# Mecanique.net
KiCad netlist of a schematic drawn in Altium Designer
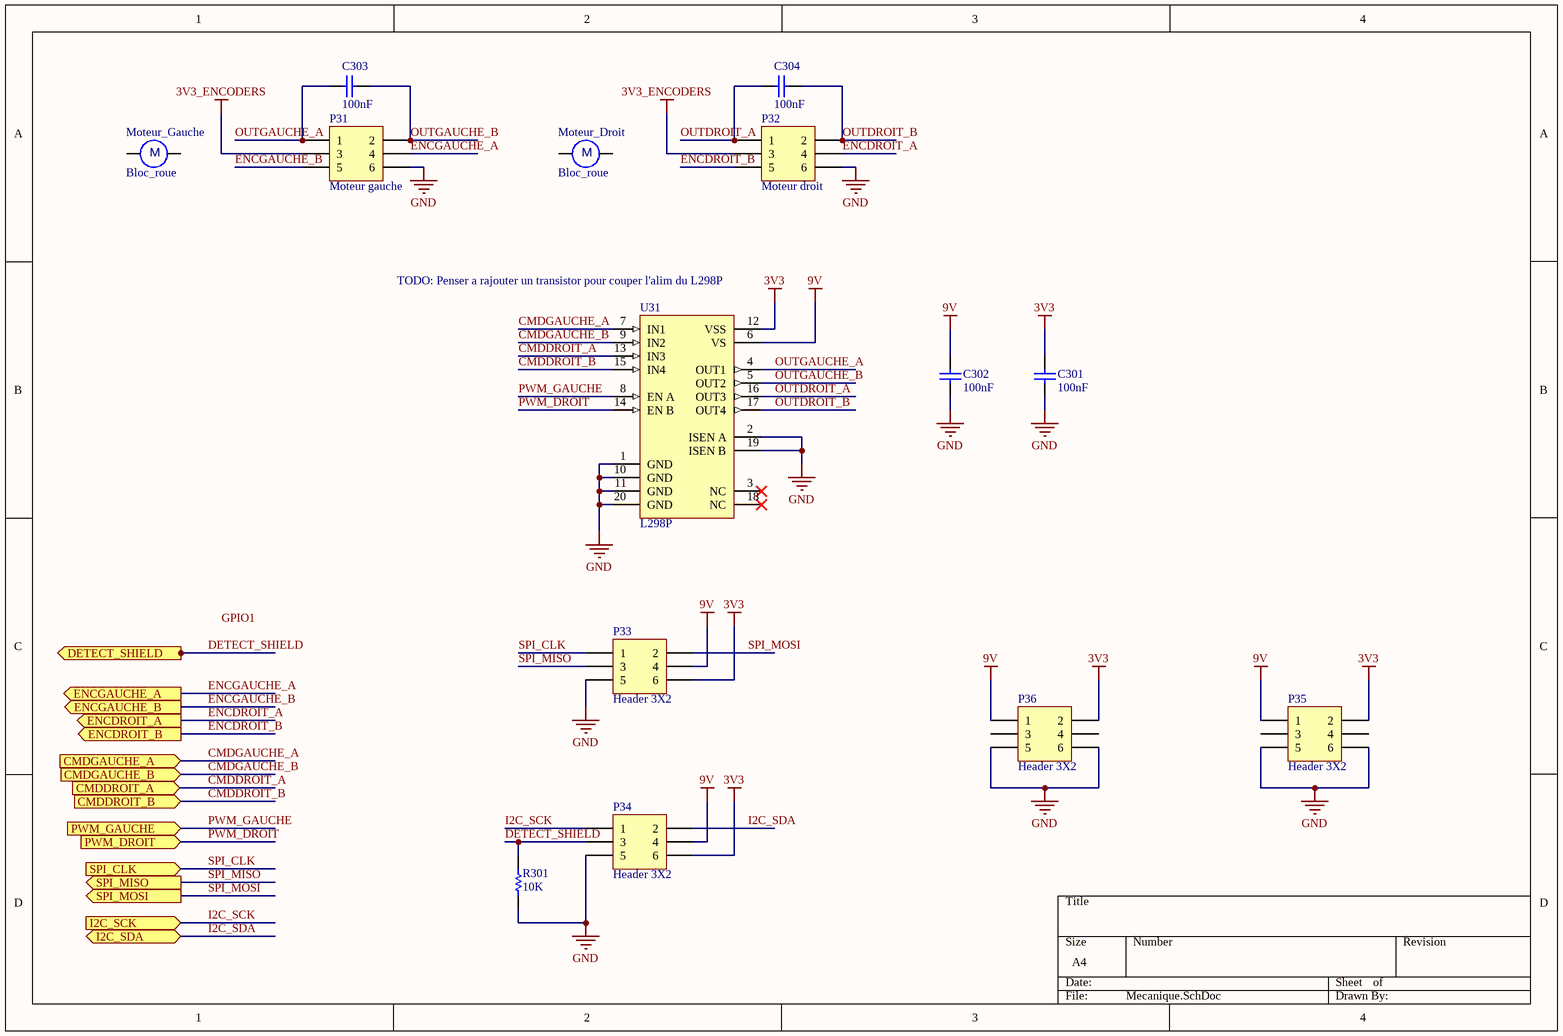
[diagram p0: Mecanique.SchDoc]

(export (version "E")
  (design (tool "Eeschema 10.0.6"))
  (components
    (comp (ref "C301")
      (value "100nF")
      (footprint "CAPC1206(3216)170_L")
      (description "CAP 100nF 50V ±10% 1206 (3216 Metric) Thickness 1.7mm SMD")
      (fields (field (name "TOLERANCE") "Â±10%") (field (name "Comment") "CAP 100nF"))
      (libsource (lib "Altium Content Vault") (part "CMP-1037-04201-1"))
    )
    (comp (ref "C302")
      (value "100nF")
      (footprint "CAPC1206(3216)170_L")
      (description "CAP 100nF 50V ±10% 1206 (3216 Metric) Thickness 1.7mm SMD")
      (fields (field (name "TOLERANCE") "Â±10%") (field (name "Comment") "CAP 100nF"))
      (libsource (lib "Altium Content Vault") (part "CMP-1037-04201-1"))
    )
    (comp (ref "C303")
      (value "100nF")
      (footprint "CAPC1206(3216)170_L")
      (description "CAP 100nF 50V ±10% 1206 (3216 Metric) Thickness 1.7mm SMD")
      (fields (field (name "TOLERANCE") "Â±10%") (field (name "Comment") "CAP 100nF"))
      (libsource (lib "Altium Content Vault") (part "CMP-1037-04201-1"))
    )
    (comp (ref "C304")
      (value "100nF")
      (footprint "CAPC1206(3216)170_L")
      (description "CAP 100nF 50V ±10% 1206 (3216 Metric) Thickness 1.7mm SMD")
      (fields (field (name "TOLERANCE") "Â±10%") (field (name "Comment") "CAP 100nF"))
      (libsource (lib "Altium Content Vault") (part "CMP-1037-04201-1"))
    )
    (comp (ref "Moteur_Droit")
      (value "Bloc_roue")
      (footprint "Bloc roue")
      (libsource (lib "Dumber 2015") (part "Bloc_roue"))
    )
    (comp (ref "Moteur_Gauche")
      (value "Bloc_roue")
      (footprint "Bloc roue")
      (libsource (lib "Dumber 2015") (part "Bloc_roue"))
    )
    (comp (ref "P31")
      (value "Moteur gauche")
      (footprint "HDR2X3")
      (description "Header, 3-Pin, Dual row")
      (fields (field (name "PUBLISHER") "Altium Limited"))
      (libsource (lib "Miscellaneous Connectors") (part "Header 3X2"))
    )
    (comp (ref "P32")
      (value "Moteur droit")
      (footprint "HDR2X3")
      (description "Header, 3-Pin, Dual row")
      (fields (field (name "PUBLISHER") "Altium Limited"))
      (libsource (lib "Miscellaneous Connectors") (part "Header 3X2"))
    )
    (comp (ref "P33")
      (value "Header 3X2")
      (footprint "HDR2X3")
      (description "Header, 3-Pin, Dual row")
      (fields (field (name "PUBLISHER") "Altium Limited"))
      (libsource (lib "Miscellaneous Connectors") (part "Header 3X2"))
    )
    (comp (ref "P34")
      (value "Header 3X2")
      (footprint "HDR2X3")
      (description "Header, 3-Pin, Dual row")
      (fields (field (name "PUBLISHER") "Altium Limited"))
      (libsource (lib "Miscellaneous Connectors") (part "Header 3X2"))
    )
    (comp (ref "P35")
      (value "Header 3X2")
      (footprint "HDR2X3")
      (description "Header, 3-Pin, Dual row")
      (fields (field (name "PUBLISHER") "Altium Limited"))
      (libsource (lib "Miscellaneous Connectors") (part "Header 3X2"))
    )
    (comp (ref "P36")
      (value "Header 3X2")
      (footprint "HDR2X3")
      (description "Header, 3-Pin, Dual row")
      (fields (field (name "PUBLISHER") "Altium Limited"))
      (libsource (lib "Miscellaneous Connectors") (part "Header 3X2"))
    )
    (comp (ref "R301")
      (value "10K")
      (footprint "RESC1206(3216)_M")
      (description "10K 0.25W 5% 1206 (3216 Metric)  SMD")
      (fields (field (name "POWER") "0.25 W") (field (name "TOLERANCE") "5 %"))
      (libsource (lib "Altium Content Vault") (part "CMP-1014-00098-1"))
    )
    (comp (ref "U31")
      (value "L298P")
      (footprint "PowerSO20_N")
      (description "Dual Full Bridge Driver")
      (fields (field (name "PUBLISHER") "Altium Limited"))
      (libsource (lib "ST Interface DC Motor Controller") (part "L298P"))
    )
  )
  (nets
    (net (code "1") (name "/CMDDROIT_A") (class "Default")
      (node (ref "U31") (pin "13") (pinfunction "IN3_13") (pintype "input"))
    )
    (net (code "2") (name "/CMDDROIT_B") (class "Default")
      (node (ref "U31") (pin "15") (pinfunction "IN4_15") (pintype "input"))
    )
    (net (code "3") (name "/CMDGAUCHE_A") (class "Default")
      (node (ref "U31") (pin "7") (pinfunction "IN1_7") (pintype "input"))
    )
    (net (code "4") (name "/CMDGAUCHE_B") (class "Default")
      (node (ref "U31") (pin "9") (pinfunction "IN2_9") (pintype "input"))
    )
    (net (code "5") (name "/DETECT_SHIELD") (class "Default")
      (node (ref "P34") (pin "3") (pinfunction "3_3") (pintype "passive"))
      (node (ref "R301") (pin "1") (pinfunction "1_1") (pintype "passive"))
    )
    (net (code "6") (name "/ENCDROIT_A") (class "Default")
      (node (ref "P32") (pin "4") (pinfunction "4_4") (pintype "passive"))
    )
    (net (code "7") (name "/ENCDROIT_B") (class "Default")
      (node (ref "P32") (pin "5") (pinfunction "5_5") (pintype "passive"))
    )
    (net (code "8") (name "/ENCGAUCHE_A") (class "Default")
      (node (ref "P31") (pin "4") (pinfunction "4_4") (pintype "passive"))
    )
    (net (code "9") (name "/ENCGAUCHE_B") (class "Default")
      (node (ref "P31") (pin "5") (pinfunction "5_5") (pintype "passive"))
    )
    (net (code "11") (name "/I2C_SCK") (class "Default")
      (node (ref "P34") (pin "1") (pinfunction "1_1") (pintype "passive"))
    )
    (net (code "12") (name "/I2C_SDA") (class "Default")
      (node (ref "P34") (pin "2") (pinfunction "2_2") (pintype "passive"))
    )
    (net (code "13") (name "/OUTDROIT_A") (class "Default")
      (node (ref "C304") (pin "2") (pinfunction "2_2") (pintype "passive"))
      (node (ref "P32") (pin "1") (pinfunction "1_1") (pintype "passive"))
      (node (ref "U31") (pin "16") (pinfunction "OUT3_16") (pintype "output"))
    )
    (net (code "14") (name "/OUTDROIT_B") (class "Default")
      (node (ref "C304") (pin "1") (pinfunction "1_1") (pintype "passive"))
      (node (ref "P32") (pin "2") (pinfunction "2_2") (pintype "passive"))
      (node (ref "U31") (pin "17") (pinfunction "OUT4_17") (pintype "output"))
    )
    (net (code "15") (name "/OUTGAUCHE_A") (class "Default")
      (node (ref "C303") (pin "2") (pinfunction "2_2") (pintype "passive"))
      (node (ref "P31") (pin "1") (pinfunction "1_1") (pintype "passive"))
      (node (ref "U31") (pin "4") (pinfunction "OUT1_4") (pintype "output"))
    )
    (net (code "16") (name "/OUTGAUCHE_B") (class "Default")
      (node (ref "C303") (pin "1") (pinfunction "1_1") (pintype "passive"))
      (node (ref "P31") (pin "2") (pinfunction "2_2") (pintype "passive"))
      (node (ref "U31") (pin "5") (pinfunction "OUT2_5") (pintype "output"))
    )
    (net (code "17") (name "/PWM_DROIT") (class "Default")
      (node (ref "U31") (pin "14") (pinfunction "EN_B_14") (pintype "input"))
    )
    (net (code "18") (name "/PWM_GAUCHE") (class "Default")
      (node (ref "U31") (pin "8") (pinfunction "EN_A_8") (pintype "input"))
    )
    (net (code "19") (name "/SPI_CLK") (class "Default")
      (node (ref "P33") (pin "1") (pinfunction "1_1") (pintype "passive"))
    )
    (net (code "20") (name "/SPI_MISO") (class "Default")
      (node (ref "P33") (pin "3") (pinfunction "3_3") (pintype "passive"))
    )
    (net (code "21") (name "/SPI_MOSI") (class "Default")
      (node (ref "P33") (pin "2") (pinfunction "2_2") (pintype "passive"))
    )
    (net (code "22") (name "3V3") (class "Default")
      (node (ref "C301") (pin "1") (pinfunction "1_1") (pintype "passive"))
      (node (ref "P33") (pin "6") (pinfunction "6_6") (pintype "passive"))
      (node (ref "P34") (pin "6") (pinfunction "6_6") (pintype "passive"))
      (node (ref "P35") (pin "2") (pinfunction "2_2") (pintype "passive"))
      (node (ref "P36") (pin "2") (pinfunction "2_2") (pintype "passive"))
      (node (ref "U31") (pin "12") (pinfunction "VSS_12") (pintype "power_in"))
    )
    (net (code "23") (name "3V3_ENCODERS") (class "Default")
      (node (ref "P31") (pin "3") (pinfunction "3_3") (pintype "passive"))
      (node (ref "P32") (pin "3") (pinfunction "3_3") (pintype "passive"))
    )
    (net (code "24") (name "9V") (class "Default")
      (node (ref "C302") (pin "1") (pinfunction "1_1") (pintype "passive"))
      (node (ref "P33") (pin "4") (pinfunction "4_4") (pintype "passive"))
      (node (ref "P34") (pin "4") (pinfunction "4_4") (pintype "passive"))
      (node (ref "P35") (pin "1") (pinfunction "1_1") (pintype "passive"))
      (node (ref "P36") (pin "1") (pinfunction "1_1") (pintype "passive"))
      (node (ref "U31") (pin "6") (pinfunction "VS_6") (pintype "power_in"))
    )
    (net (code "25") (name "GND") (class "Default")
      (node (ref "C301") (pin "2") (pinfunction "2_2") (pintype "passive"))
      (node (ref "C302") (pin "2") (pinfunction "2_2") (pintype "passive"))
      (node (ref "P31") (pin "6") (pinfunction "6_6") (pintype "passive"))
      (node (ref "P32") (pin "6") (pinfunction "6_6") (pintype "passive"))
      (node (ref "P33") (pin "5") (pinfunction "5_5") (pintype "passive"))
      (node (ref "P34") (pin "5") (pinfunction "5_5") (pintype "passive"))
      (node (ref "P35") (pin "5") (pinfunction "5_5") (pintype "passive"))
      (node (ref "P35") (pin "6") (pinfunction "6_6") (pintype "passive"))
      (node (ref "P36") (pin "5") (pinfunction "5_5") (pintype "passive"))
      (node (ref "P36") (pin "6") (pinfunction "6_6") (pintype "passive"))
      (node (ref "R301") (pin "2") (pinfunction "2_2") (pintype "passive"))
      (node (ref "U31") (pin "1") (pinfunction "GND_1") (pintype "power_in"))
      (node (ref "U31") (pin "10") (pinfunction "GND_10") (pintype "power_in"))
      (node (ref "U31") (pin "11") (pinfunction "GND_11") (pintype "power_in"))
      (node (ref "U31") (pin "19") (pinfunction "ISEN_B_19") (pintype "passive"))
      (node (ref "U31") (pin "2") (pinfunction "ISEN_A_2") (pintype "passive"))
      (node (ref "U31") (pin "20") (pinfunction "GND_20") (pintype "power_in"))
    )
    (net (code "26") (name "unconnected-(P35-Pad3)") (class "Default")
      (node (ref "P35") (pin "3") (pinfunction "3_3") (pintype "passive"))
    )
    (net (code "27") (name "unconnected-(P35-Pad4)") (class "Default")
      (node (ref "P35") (pin "4") (pinfunction "4_4") (pintype "passive"))
    )
    (net (code "28") (name "unconnected-(P36-Pad3)") (class "Default")
      (node (ref "P36") (pin "3") (pinfunction "3_3") (pintype "passive"))
    )
    (net (code "29") (name "unconnected-(P36-Pad4)") (class "Default")
      (node (ref "P36") (pin "4") (pinfunction "4_4") (pintype "passive"))
    )
    (net (code "30") (name "unconnected-(U31-NC-Pad3)") (class "Default")
      (node (ref "U31") (pin "3") (pinfunction "NC_3") (pintype "passive+no_connect"))
    )
    (net (code "31") (name "unconnected-(U31-NC-Pad18)") (class "Default")
      (node (ref "U31") (pin "18") (pinfunction "NC_18") (pintype "passive+no_connect"))
    )
  )
)
